# sk6812-24-12ring-out.net
KiCad netlist of a schematic drawn in EAGLE
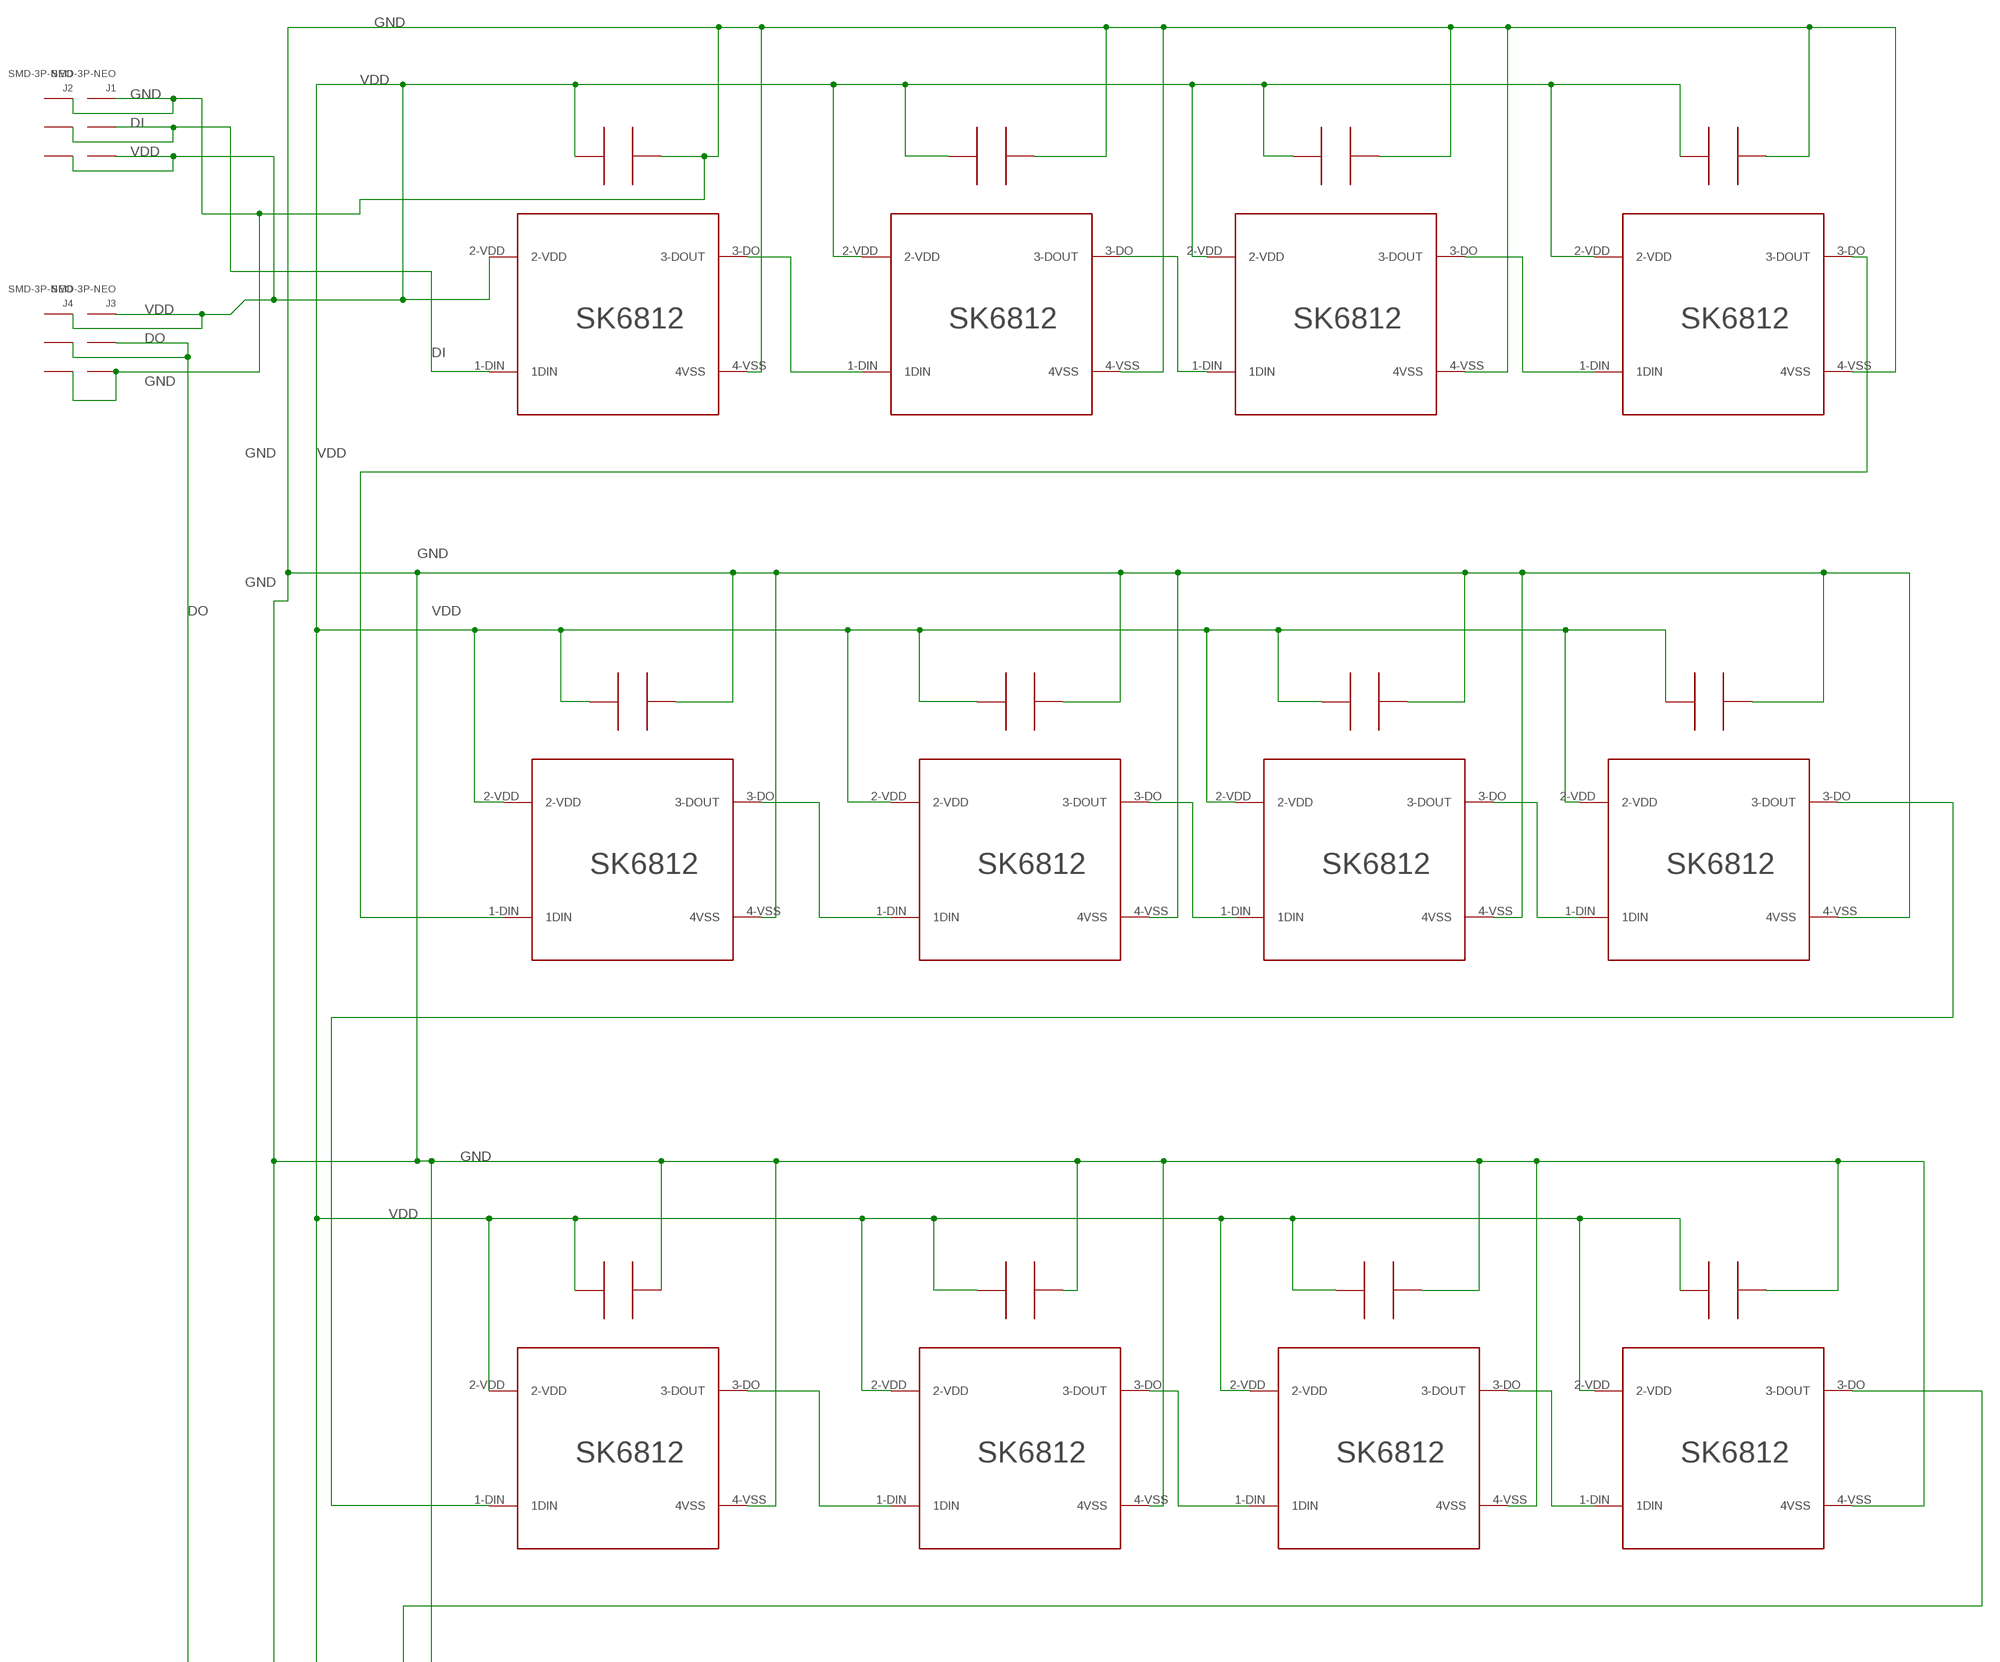
[diagram p0: schematic, sheet 1, part 1 of 2]
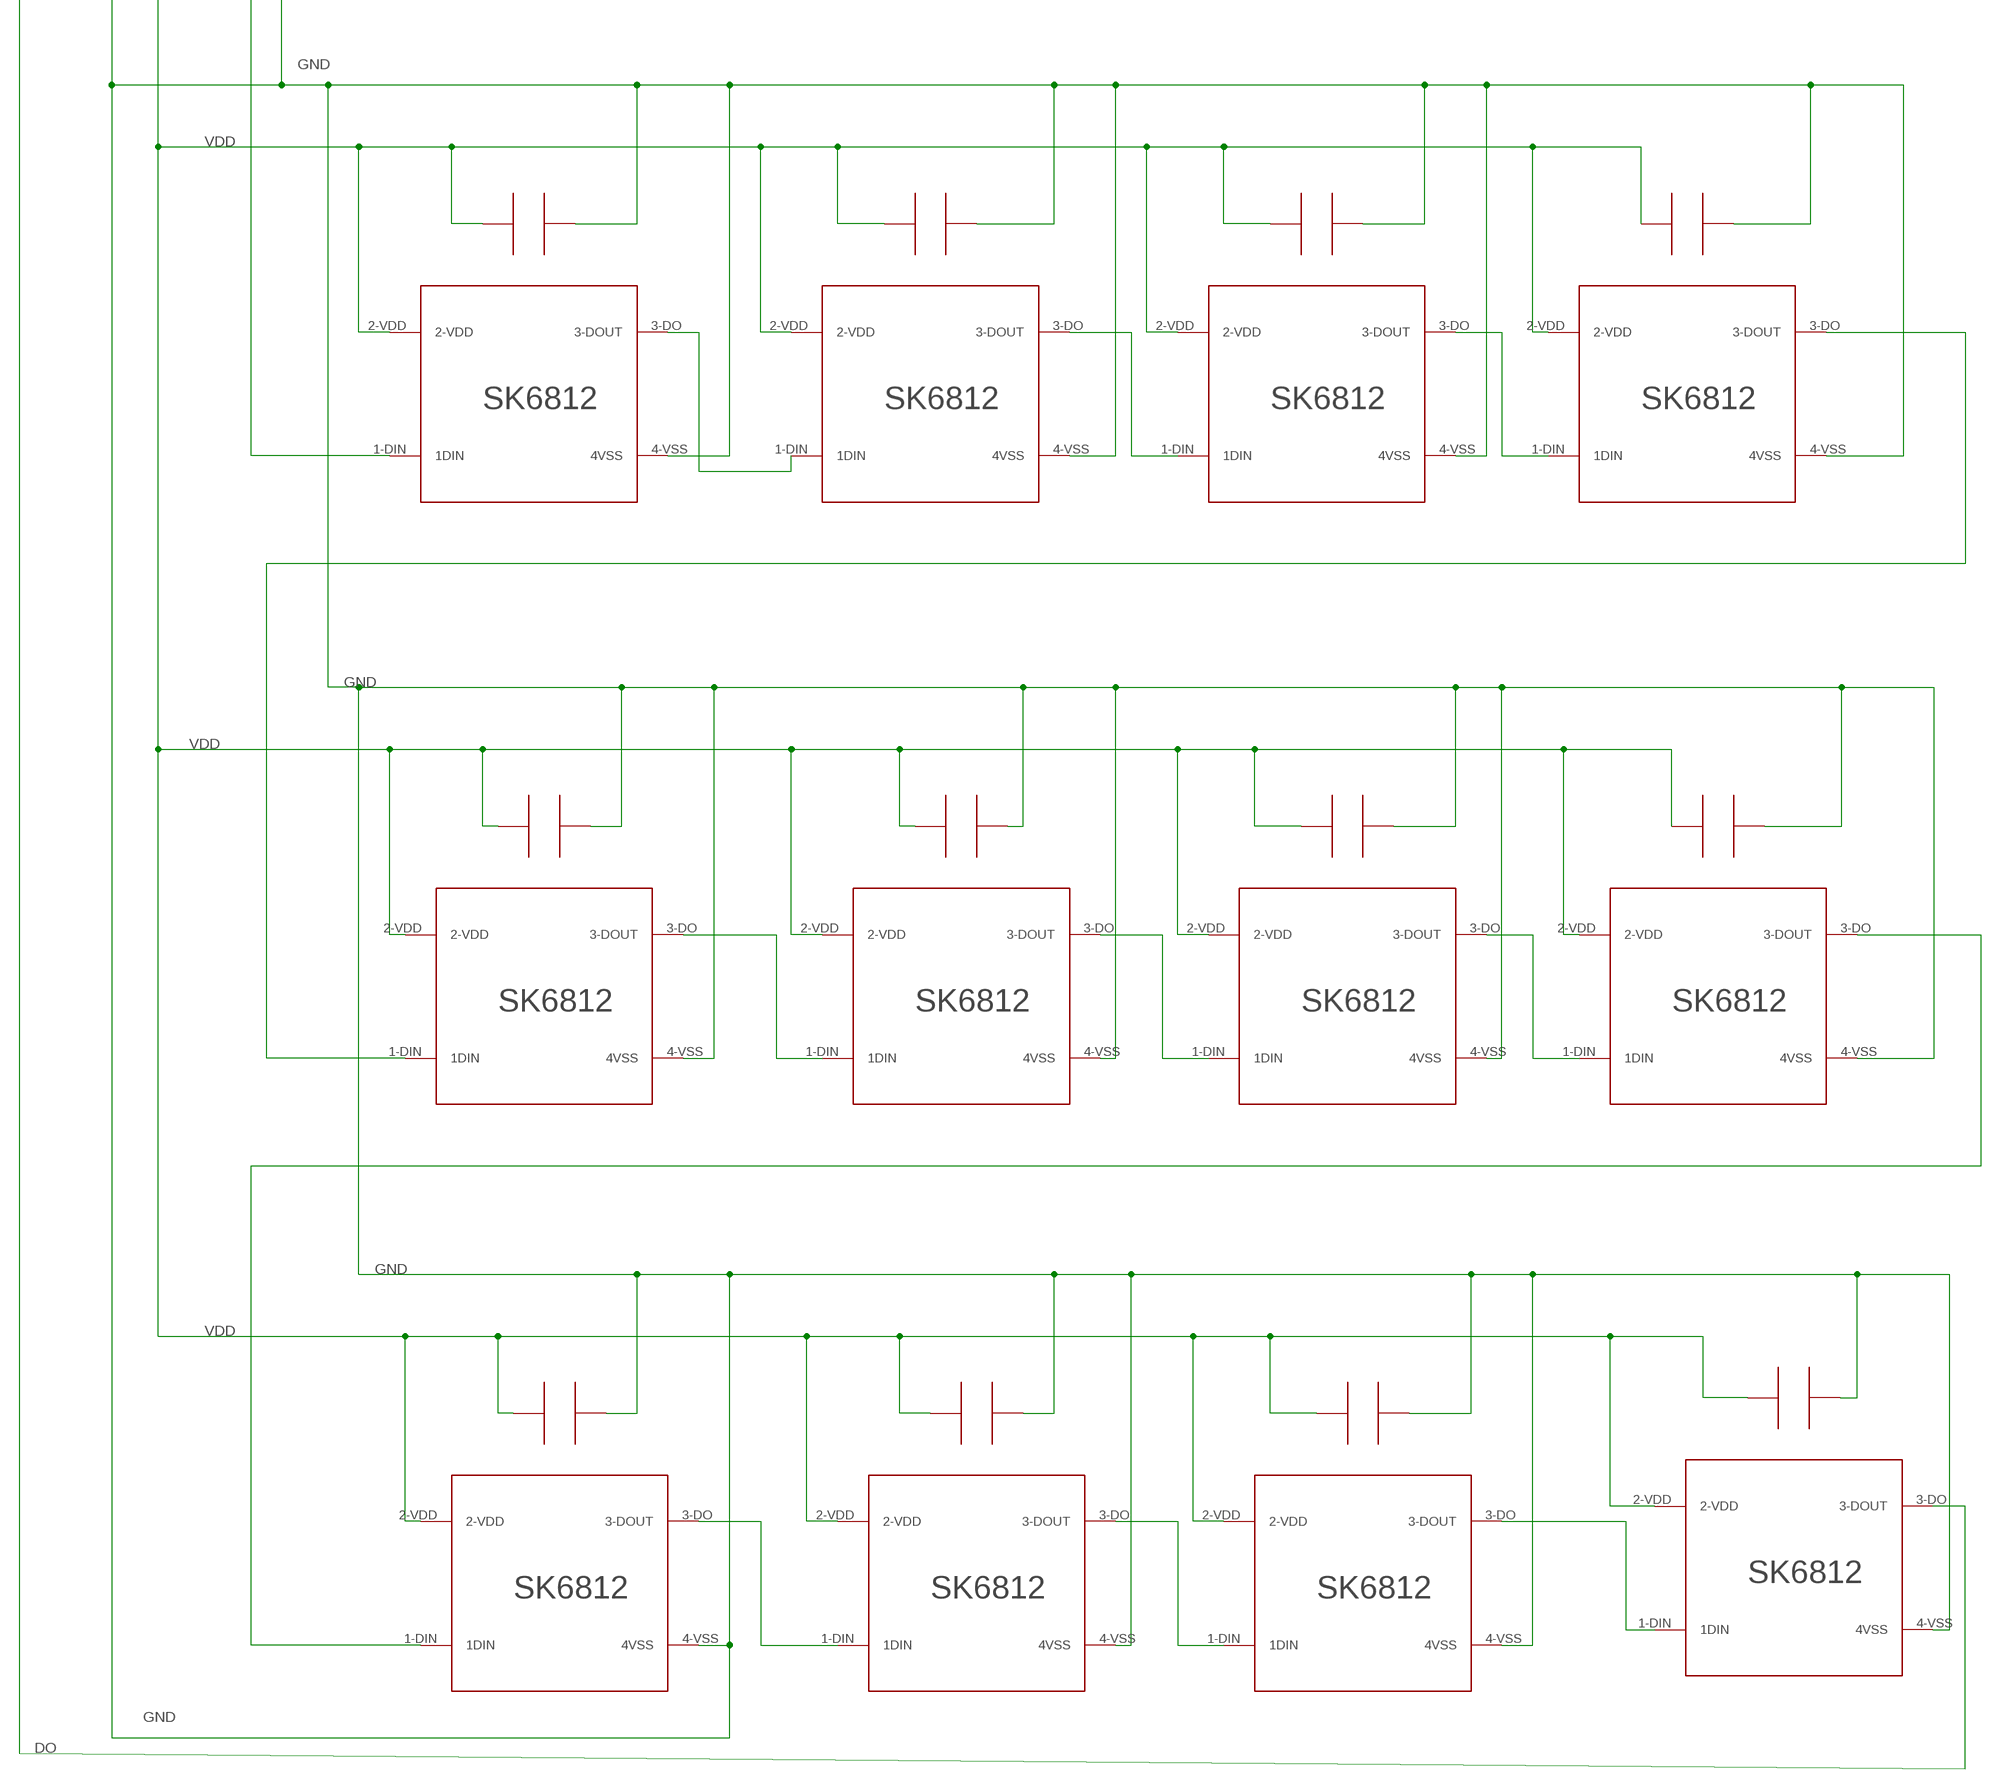
[diagram p1: schematic, sheet 1, part 2 of 2]

(export (version "E")
  (design (tool "Eeschema 10.0.6"))
  (components
    (comp (ref "D1")
      (value "SK6812-S-C")
      (footprint "eagle-import:SMD4020+0402C")
      (libsource (lib "eagle-import") (part "SK6812-S-C"))
    )
    (comp (ref "D2")
      (value "SK6812-S-C")
      (footprint "eagle-import:SMD4020+0402C")
      (libsource (lib "eagle-import") (part "SK6812-S-C"))
    )
    (comp (ref "D3")
      (value "SK6812-S-C")
      (footprint "eagle-import:SMD4020+0402C")
      (libsource (lib "eagle-import") (part "SK6812-S-C"))
    )
    (comp (ref "D4")
      (value "SK6812-S-C")
      (footprint "eagle-import:SMD4020+0402C")
      (libsource (lib "eagle-import") (part "SK6812-S-C"))
    )
    (comp (ref "D5")
      (value "SK6812-S-C")
      (footprint "eagle-import:SMD4020+0402C")
      (libsource (lib "eagle-import") (part "SK6812-S-C"))
    )
    (comp (ref "D6")
      (value "SK6812-S-C")
      (footprint "eagle-import:SMD4020+0402C")
      (libsource (lib "eagle-import") (part "SK6812-S-C"))
    )
    (comp (ref "D7")
      (value "SK6812-S-C")
      (footprint "eagle-import:SMD4020+0402C")
      (libsource (lib "eagle-import") (part "SK6812-S-C"))
    )
    (comp (ref "D8")
      (value "SK6812-S-C")
      (footprint "eagle-import:SMD4020+0402C")
      (libsource (lib "eagle-import") (part "SK6812-S-C"))
    )
    (comp (ref "D9")
      (value "SK6812-S-C")
      (footprint "eagle-import:SMD4020+0402C")
      (libsource (lib "eagle-import") (part "SK6812-S-C"))
    )
    (comp (ref "D10")
      (value "SK6812-S-C")
      (footprint "eagle-import:SMD4020+0402C")
      (libsource (lib "eagle-import") (part "SK6812-S-C"))
    )
    (comp (ref "D11")
      (value "SK6812-S-C")
      (footprint "eagle-import:SMD4020+0402C")
      (libsource (lib "eagle-import") (part "SK6812-S-C"))
    )
    (comp (ref "D12")
      (value "SK6812-S-C")
      (footprint "eagle-import:SMD4020+0402C")
      (libsource (lib "eagle-import") (part "SK6812-S-C"))
    )
    (comp (ref "D13")
      (value "SK6812-S-C")
      (footprint "eagle-import:SMD4020+0402C")
      (libsource (lib "eagle-import") (part "SK6812-S-C"))
    )
    (comp (ref "D14")
      (value "SK6812-S-C")
      (footprint "eagle-import:SMD4020+0402C")
      (libsource (lib "eagle-import") (part "SK6812-S-C"))
    )
    (comp (ref "D15")
      (value "SK6812-S-C")
      (footprint "eagle-import:SMD4020+0402C")
      (libsource (lib "eagle-import") (part "SK6812-S-C"))
    )
    (comp (ref "D16")
      (value "SK6812-S-C")
      (footprint "eagle-import:SMD4020+0402C")
      (libsource (lib "eagle-import") (part "SK6812-S-C"))
    )
    (comp (ref "D17")
      (value "SK6812-S-C")
      (footprint "eagle-import:SMD4020+0402C")
      (libsource (lib "eagle-import") (part "SK6812-S-C"))
    )
    (comp (ref "D18")
      (value "SK6812-S-C")
      (footprint "eagle-import:SMD4020+0402C")
      (libsource (lib "eagle-import") (part "SK6812-S-C"))
    )
    (comp (ref "D19")
      (value "SK6812-S-C")
      (footprint "eagle-import:SMD4020+0402C")
      (libsource (lib "eagle-import") (part "SK6812-S-C"))
    )
    (comp (ref "D20")
      (value "SK6812-S-C")
      (footprint "eagle-import:SMD4020+0402C")
      (libsource (lib "eagle-import") (part "SK6812-S-C"))
    )
    (comp (ref "D21")
      (value "SK6812-S-C")
      (footprint "eagle-import:SMD4020+0402C")
      (libsource (lib "eagle-import") (part "SK6812-S-C"))
    )
    (comp (ref "D22")
      (value "SK6812-S-C")
      (footprint "eagle-import:SMD4020+0402C")
      (libsource (lib "eagle-import") (part "SK6812-S-C"))
    )
    (comp (ref "D23")
      (value "SK6812-S-C")
      (footprint "eagle-import:SMD4020+0402C")
      (libsource (lib "eagle-import") (part "SK6812-S-C"))
    )
    (comp (ref "D24")
      (value "SK6812-S-C")
      (footprint "eagle-import:SMD4020+0402C")
      (libsource (lib "eagle-import") (part "SK6812-S-C"))
    )
    (comp (ref "J1")
      (value "SMD-3P-NEO")
      (footprint "eagle-import:SMD-3P-2.0")
      (libsource (lib "eagle-import") (part "SMD-3P-NEO"))
    )
    (comp (ref "J2")
      (value "SMD-3P-NEO")
      (footprint "eagle-import:SMD-3P-2.0")
      (libsource (lib "eagle-import") (part "SMD-3P-NEO"))
    )
    (comp (ref "J3")
      (value "SMD-3P-NEO")
      (footprint "eagle-import:SMD-3P-2.0")
      (libsource (lib "eagle-import") (part "SMD-3P-NEO"))
    )
    (comp (ref "J4")
      (value "SMD-3P-NEO")
      (footprint "eagle-import:SMD-3P-2.0")
      (libsource (lib "eagle-import") (part "SMD-3P-NEO"))
    )
  )
  (nets
    (net (code "1") (name "/DI") (class "Default")
      (node (ref "D1") (pin "1-DIN") (pinfunction "1DIN_1-DIN") (pintype "bidirectional"))
      (node (ref "J1") (pin "P$2") (pinfunction "2_P$2") (pintype "bidirectional"))
      (node (ref "J2") (pin "P$2") (pinfunction "2_P$2") (pintype "bidirectional"))
    )
    (net (code "2") (name "/DO") (class "Default")
      (node (ref "D24") (pin "3-DO") (pinfunction "3-DOUT_3-DO") (pintype "bidirectional"))
      (node (ref "J3") (pin "P$2") (pinfunction "2_P$2") (pintype "bidirectional"))
      (node (ref "J4") (pin "P$2") (pinfunction "2_P$2") (pintype "bidirectional"))
    )
    (net (code "3") (name "/GND") (class "Default")
      (node (ref "D1") (pin "4-VSS") (pinfunction "4VSS_4-VSS") (pintype "bidirectional"))
      (node (ref "D1") (pin "5-C-VSS") (pinfunction "C-VSS_5-C-VSS") (pintype "bidirectional"))
      (node (ref "D10") (pin "4-VSS") (pinfunction "4VSS_4-VSS") (pintype "bidirectional"))
      (node (ref "D10") (pin "5-C-VSS") (pinfunction "C-VSS_5-C-VSS") (pintype "bidirectional"))
      (node (ref "D11") (pin "4-VSS") (pinfunction "4VSS_4-VSS") (pintype "bidirectional"))
      (node (ref "D11") (pin "5-C-VSS") (pinfunction "C-VSS_5-C-VSS") (pintype "bidirectional"))
      (node (ref "D12") (pin "4-VSS") (pinfunction "4VSS_4-VSS") (pintype "bidirectional"))
      (node (ref "D12") (pin "5-C-VSS") (pinfunction "C-VSS_5-C-VSS") (pintype "bidirectional"))
      (node (ref "D13") (pin "4-VSS") (pinfunction "4VSS_4-VSS") (pintype "bidirectional"))
      (node (ref "D13") (pin "5-C-VSS") (pinfunction "C-VSS_5-C-VSS") (pintype "bidirectional"))
      (node (ref "D14") (pin "4-VSS") (pinfunction "4VSS_4-VSS") (pintype "bidirectional"))
      (node (ref "D14") (pin "5-C-VSS") (pinfunction "C-VSS_5-C-VSS") (pintype "bidirectional"))
      (node (ref "D15") (pin "4-VSS") (pinfunction "4VSS_4-VSS") (pintype "bidirectional"))
      (node (ref "D15") (pin "5-C-VSS") (pinfunction "C-VSS_5-C-VSS") (pintype "bidirectional"))
      (node (ref "D16") (pin "4-VSS") (pinfunction "4VSS_4-VSS") (pintype "bidirectional"))
      (node (ref "D16") (pin "5-C-VSS") (pinfunction "C-VSS_5-C-VSS") (pintype "bidirectional"))
      (node (ref "D17") (pin "4-VSS") (pinfunction "4VSS_4-VSS") (pintype "bidirectional"))
      (node (ref "D17") (pin "5-C-VSS") (pinfunction "C-VSS_5-C-VSS") (pintype "bidirectional"))
      (node (ref "D18") (pin "4-VSS") (pinfunction "4VSS_4-VSS") (pintype "bidirectional"))
      (node (ref "D18") (pin "5-C-VSS") (pinfunction "C-VSS_5-C-VSS") (pintype "bidirectional"))
      (node (ref "D19") (pin "4-VSS") (pinfunction "4VSS_4-VSS") (pintype "bidirectional"))
      (node (ref "D19") (pin "5-C-VSS") (pinfunction "C-VSS_5-C-VSS") (pintype "bidirectional"))
      (node (ref "D2") (pin "4-VSS") (pinfunction "4VSS_4-VSS") (pintype "bidirectional"))
      (node (ref "D2") (pin "5-C-VSS") (pinfunction "C-VSS_5-C-VSS") (pintype "bidirectional"))
      (node (ref "D20") (pin "4-VSS") (pinfunction "4VSS_4-VSS") (pintype "bidirectional"))
      (node (ref "D20") (pin "5-C-VSS") (pinfunction "C-VSS_5-C-VSS") (pintype "bidirectional"))
      (node (ref "D21") (pin "4-VSS") (pinfunction "4VSS_4-VSS") (pintype "bidirectional"))
      (node (ref "D21") (pin "5-C-VSS") (pinfunction "C-VSS_5-C-VSS") (pintype "bidirectional"))
      (node (ref "D22") (pin "4-VSS") (pinfunction "4VSS_4-VSS") (pintype "bidirectional"))
      (node (ref "D22") (pin "5-C-VSS") (pinfunction "C-VSS_5-C-VSS") (pintype "bidirectional"))
      (node (ref "D23") (pin "4-VSS") (pinfunction "4VSS_4-VSS") (pintype "bidirectional"))
      (node (ref "D23") (pin "5-C-VSS") (pinfunction "C-VSS_5-C-VSS") (pintype "bidirectional"))
      (node (ref "D24") (pin "4-VSS") (pinfunction "4VSS_4-VSS") (pintype "bidirectional"))
      (node (ref "D24") (pin "5-C-VSS") (pinfunction "C-VSS_5-C-VSS") (pintype "bidirectional"))
      (node (ref "D3") (pin "4-VSS") (pinfunction "4VSS_4-VSS") (pintype "bidirectional"))
      (node (ref "D3") (pin "5-C-VSS") (pinfunction "C-VSS_5-C-VSS") (pintype "bidirectional"))
      (node (ref "D4") (pin "4-VSS") (pinfunction "4VSS_4-VSS") (pintype "bidirectional"))
      (node (ref "D4") (pin "5-C-VSS") (pinfunction "C-VSS_5-C-VSS") (pintype "bidirectional"))
      (node (ref "D5") (pin "4-VSS") (pinfunction "4VSS_4-VSS") (pintype "bidirectional"))
      (node (ref "D5") (pin "5-C-VSS") (pinfunction "C-VSS_5-C-VSS") (pintype "bidirectional"))
      (node (ref "D6") (pin "4-VSS") (pinfunction "4VSS_4-VSS") (pintype "bidirectional"))
      (node (ref "D6") (pin "5-C-VSS") (pinfunction "C-VSS_5-C-VSS") (pintype "bidirectional"))
      (node (ref "D7") (pin "4-VSS") (pinfunction "4VSS_4-VSS") (pintype "bidirectional"))
      (node (ref "D7") (pin "5-C-VSS") (pinfunction "C-VSS_5-C-VSS") (pintype "bidirectional"))
      (node (ref "D8") (pin "4-VSS") (pinfunction "4VSS_4-VSS") (pintype "bidirectional"))
      (node (ref "D8") (pin "5-C-VSS") (pinfunction "C-VSS_5-C-VSS") (pintype "bidirectional"))
      (node (ref "D9") (pin "4-VSS") (pinfunction "4VSS_4-VSS") (pintype "bidirectional"))
      (node (ref "D9") (pin "5-C-VSS") (pinfunction "C-VSS_5-C-VSS") (pintype "bidirectional"))
      (node (ref "J1") (pin "P$3") (pinfunction "3_P$3") (pintype "bidirectional"))
      (node (ref "J2") (pin "P$3") (pinfunction "3_P$3") (pintype "bidirectional"))
      (node (ref "J3") (pin "P$1") (pinfunction "1_P$1") (pintype "bidirectional"))
      (node (ref "J4") (pin "P$1") (pinfunction "1_P$1") (pintype "bidirectional"))
    )
    (net (code "4") (name "/VDD") (class "Default")
      (node (ref "D1") (pin "2-VDD") (pinfunction "2-VDD_2-VDD") (pintype "bidirectional"))
      (node (ref "D1") (pin "6-C-VDD") (pinfunction "C-VDD_6-C-VDD") (pintype "bidirectional"))
      (node (ref "D10") (pin "2-VDD") (pinfunction "2-VDD_2-VDD") (pintype "bidirectional"))
      (node (ref "D10") (pin "6-C-VDD") (pinfunction "C-VDD_6-C-VDD") (pintype "bidirectional"))
      (node (ref "D11") (pin "2-VDD") (pinfunction "2-VDD_2-VDD") (pintype "bidirectional"))
      (node (ref "D11") (pin "6-C-VDD") (pinfunction "C-VDD_6-C-VDD") (pintype "bidirectional"))
      (node (ref "D12") (pin "2-VDD") (pinfunction "2-VDD_2-VDD") (pintype "bidirectional"))
      (node (ref "D12") (pin "6-C-VDD") (pinfunction "C-VDD_6-C-VDD") (pintype "bidirectional"))
      (node (ref "D13") (pin "2-VDD") (pinfunction "2-VDD_2-VDD") (pintype "bidirectional"))
      (node (ref "D13") (pin "6-C-VDD") (pinfunction "C-VDD_6-C-VDD") (pintype "bidirectional"))
      (node (ref "D14") (pin "2-VDD") (pinfunction "2-VDD_2-VDD") (pintype "bidirectional"))
      (node (ref "D14") (pin "6-C-VDD") (pinfunction "C-VDD_6-C-VDD") (pintype "bidirectional"))
      (node (ref "D15") (pin "2-VDD") (pinfunction "2-VDD_2-VDD") (pintype "bidirectional"))
      (node (ref "D15") (pin "6-C-VDD") (pinfunction "C-VDD_6-C-VDD") (pintype "bidirectional"))
      (node (ref "D16") (pin "2-VDD") (pinfunction "2-VDD_2-VDD") (pintype "bidirectional"))
      (node (ref "D16") (pin "6-C-VDD") (pinfunction "C-VDD_6-C-VDD") (pintype "bidirectional"))
      (node (ref "D17") (pin "2-VDD") (pinfunction "2-VDD_2-VDD") (pintype "bidirectional"))
      (node (ref "D17") (pin "6-C-VDD") (pinfunction "C-VDD_6-C-VDD") (pintype "bidirectional"))
      (node (ref "D18") (pin "2-VDD") (pinfunction "2-VDD_2-VDD") (pintype "bidirectional"))
      (node (ref "D18") (pin "6-C-VDD") (pinfunction "C-VDD_6-C-VDD") (pintype "bidirectional"))
      (node (ref "D19") (pin "2-VDD") (pinfunction "2-VDD_2-VDD") (pintype "bidirectional"))
      (node (ref "D19") (pin "6-C-VDD") (pinfunction "C-VDD_6-C-VDD") (pintype "bidirectional"))
      (node (ref "D2") (pin "2-VDD") (pinfunction "2-VDD_2-VDD") (pintype "bidirectional"))
      (node (ref "D2") (pin "6-C-VDD") (pinfunction "C-VDD_6-C-VDD") (pintype "bidirectional"))
      (node (ref "D20") (pin "2-VDD") (pinfunction "2-VDD_2-VDD") (pintype "bidirectional"))
      (node (ref "D20") (pin "6-C-VDD") (pinfunction "C-VDD_6-C-VDD") (pintype "bidirectional"))
      (node (ref "D21") (pin "2-VDD") (pinfunction "2-VDD_2-VDD") (pintype "bidirectional"))
      (node (ref "D21") (pin "6-C-VDD") (pinfunction "C-VDD_6-C-VDD") (pintype "bidirectional"))
      (node (ref "D22") (pin "2-VDD") (pinfunction "2-VDD_2-VDD") (pintype "bidirectional"))
      (node (ref "D22") (pin "6-C-VDD") (pinfunction "C-VDD_6-C-VDD") (pintype "bidirectional"))
      (node (ref "D23") (pin "2-VDD") (pinfunction "2-VDD_2-VDD") (pintype "bidirectional"))
      (node (ref "D23") (pin "6-C-VDD") (pinfunction "C-VDD_6-C-VDD") (pintype "bidirectional"))
      (node (ref "D24") (pin "2-VDD") (pinfunction "2-VDD_2-VDD") (pintype "bidirectional"))
      (node (ref "D24") (pin "6-C-VDD") (pinfunction "C-VDD_6-C-VDD") (pintype "bidirectional"))
      (node (ref "D3") (pin "2-VDD") (pinfunction "2-VDD_2-VDD") (pintype "bidirectional"))
      (node (ref "D3") (pin "6-C-VDD") (pinfunction "C-VDD_6-C-VDD") (pintype "bidirectional"))
      (node (ref "D4") (pin "2-VDD") (pinfunction "2-VDD_2-VDD") (pintype "bidirectional"))
      (node (ref "D4") (pin "6-C-VDD") (pinfunction "C-VDD_6-C-VDD") (pintype "bidirectional"))
      (node (ref "D5") (pin "2-VDD") (pinfunction "2-VDD_2-VDD") (pintype "bidirectional"))
      (node (ref "D5") (pin "6-C-VDD") (pinfunction "C-VDD_6-C-VDD") (pintype "bidirectional"))
      (node (ref "D6") (pin "2-VDD") (pinfunction "2-VDD_2-VDD") (pintype "bidirectional"))
      (node (ref "D6") (pin "6-C-VDD") (pinfunction "C-VDD_6-C-VDD") (pintype "bidirectional"))
      (node (ref "D7") (pin "2-VDD") (pinfunction "2-VDD_2-VDD") (pintype "bidirectional"))
      (node (ref "D7") (pin "6-C-VDD") (pinfunction "C-VDD_6-C-VDD") (pintype "bidirectional"))
      (node (ref "D8") (pin "2-VDD") (pinfunction "2-VDD_2-VDD") (pintype "bidirectional"))
      (node (ref "D8") (pin "6-C-VDD") (pinfunction "C-VDD_6-C-VDD") (pintype "bidirectional"))
      (node (ref "D9") (pin "2-VDD") (pinfunction "2-VDD_2-VDD") (pintype "bidirectional"))
      (node (ref "D9") (pin "6-C-VDD") (pinfunction "C-VDD_6-C-VDD") (pintype "bidirectional"))
      (node (ref "J1") (pin "P$1") (pinfunction "1_P$1") (pintype "bidirectional"))
      (node (ref "J2") (pin "P$1") (pinfunction "1_P$1") (pintype "bidirectional"))
      (node (ref "J3") (pin "P$3") (pinfunction "3_P$3") (pintype "bidirectional"))
      (node (ref "J4") (pin "P$3") (pinfunction "3_P$3") (pintype "bidirectional"))
    )
    (net (code "5") (name "Net-(D1-3-DOUT)") (class "Default")
      (node (ref "D1") (pin "3-DO") (pinfunction "3-DOUT_3-DO") (pintype "bidirectional"))
      (node (ref "D2") (pin "1-DIN") (pinfunction "1DIN_1-DIN") (pintype "bidirectional"))
    )
    (net (code "6") (name "Net-(D2-3-DOUT)") (class "Default")
      (node (ref "D2") (pin "3-DO") (pinfunction "3-DOUT_3-DO") (pintype "bidirectional"))
      (node (ref "D3") (pin "1-DIN") (pinfunction "1DIN_1-DIN") (pintype "bidirectional"))
    )
    (net (code "7") (name "Net-(D3-3-DOUT)") (class "Default")
      (node (ref "D3") (pin "3-DO") (pinfunction "3-DOUT_3-DO") (pintype "bidirectional"))
      (node (ref "D4") (pin "1-DIN") (pinfunction "1DIN_1-DIN") (pintype "bidirectional"))
    )
    (net (code "8") (name "Net-(D4-3-DOUT)") (class "Default")
      (node (ref "D4") (pin "3-DO") (pinfunction "3-DOUT_3-DO") (pintype "bidirectional"))
      (node (ref "D5") (pin "1-DIN") (pinfunction "1DIN_1-DIN") (pintype "bidirectional"))
    )
    (net (code "9") (name "Net-(D5-3-DOUT)") (class "Default")
      (node (ref "D5") (pin "3-DO") (pinfunction "3-DOUT_3-DO") (pintype "bidirectional"))
      (node (ref "D6") (pin "1-DIN") (pinfunction "1DIN_1-DIN") (pintype "bidirectional"))
    )
    (net (code "10") (name "Net-(D6-3-DOUT)") (class "Default")
      (node (ref "D6") (pin "3-DO") (pinfunction "3-DOUT_3-DO") (pintype "bidirectional"))
      (node (ref "D7") (pin "1-DIN") (pinfunction "1DIN_1-DIN") (pintype "bidirectional"))
    )
    (net (code "11") (name "Net-(D7-3-DOUT)") (class "Default")
      (node (ref "D7") (pin "3-DO") (pinfunction "3-DOUT_3-DO") (pintype "bidirectional"))
      (node (ref "D8") (pin "1-DIN") (pinfunction "1DIN_1-DIN") (pintype "bidirectional"))
    )
    (net (code "12") (name "Net-(D8-3-DOUT)") (class "Default")
      (node (ref "D8") (pin "3-DO") (pinfunction "3-DOUT_3-DO") (pintype "bidirectional"))
      (node (ref "D9") (pin "1-DIN") (pinfunction "1DIN_1-DIN") (pintype "bidirectional"))
    )
    (net (code "13") (name "Net-(D10-1DIN)") (class "Default")
      (node (ref "D10") (pin "1-DIN") (pinfunction "1DIN_1-DIN") (pintype "bidirectional"))
      (node (ref "D9") (pin "3-DO") (pinfunction "3-DOUT_3-DO") (pintype "bidirectional"))
    )
    (net (code "14") (name "Net-(D10-3-DOUT)") (class "Default")
      (node (ref "D10") (pin "3-DO") (pinfunction "3-DOUT_3-DO") (pintype "bidirectional"))
      (node (ref "D11") (pin "1-DIN") (pinfunction "1DIN_1-DIN") (pintype "bidirectional"))
    )
    (net (code "15") (name "Net-(D11-3-DOUT)") (class "Default")
      (node (ref "D11") (pin "3-DO") (pinfunction "3-DOUT_3-DO") (pintype "bidirectional"))
      (node (ref "D12") (pin "1-DIN") (pinfunction "1DIN_1-DIN") (pintype "bidirectional"))
    )
    (net (code "16") (name "Net-(D12-3-DOUT)") (class "Default")
      (node (ref "D12") (pin "3-DO") (pinfunction "3-DOUT_3-DO") (pintype "bidirectional"))
      (node (ref "D13") (pin "1-DIN") (pinfunction "1DIN_1-DIN") (pintype "bidirectional"))
    )
    (net (code "17") (name "Net-(D13-3-DOUT)") (class "Default")
      (node (ref "D13") (pin "3-DO") (pinfunction "3-DOUT_3-DO") (pintype "bidirectional"))
      (node (ref "D14") (pin "1-DIN") (pinfunction "1DIN_1-DIN") (pintype "bidirectional"))
    )
    (net (code "18") (name "Net-(D14-3-DOUT)") (class "Default")
      (node (ref "D14") (pin "3-DO") (pinfunction "3-DOUT_3-DO") (pintype "bidirectional"))
      (node (ref "D15") (pin "1-DIN") (pinfunction "1DIN_1-DIN") (pintype "bidirectional"))
    )
    (net (code "19") (name "Net-(D15-3-DOUT)") (class "Default")
      (node (ref "D15") (pin "3-DO") (pinfunction "3-DOUT_3-DO") (pintype "bidirectional"))
      (node (ref "D16") (pin "1-DIN") (pinfunction "1DIN_1-DIN") (pintype "bidirectional"))
    )
    (net (code "20") (name "Net-(D16-3-DOUT)") (class "Default")
      (node (ref "D16") (pin "3-DO") (pinfunction "3-DOUT_3-DO") (pintype "bidirectional"))
      (node (ref "D17") (pin "1-DIN") (pinfunction "1DIN_1-DIN") (pintype "bidirectional"))
    )
    (net (code "21") (name "Net-(D17-3-DOUT)") (class "Default")
      (node (ref "D17") (pin "3-DO") (pinfunction "3-DOUT_3-DO") (pintype "bidirectional"))
      (node (ref "D18") (pin "1-DIN") (pinfunction "1DIN_1-DIN") (pintype "bidirectional"))
    )
    (net (code "22") (name "Net-(D18-3-DOUT)") (class "Default")
      (node (ref "D18") (pin "3-DO") (pinfunction "3-DOUT_3-DO") (pintype "bidirectional"))
      (node (ref "D19") (pin "1-DIN") (pinfunction "1DIN_1-DIN") (pintype "bidirectional"))
    )
    (net (code "23") (name "Net-(D19-3-DOUT)") (class "Default")
      (node (ref "D19") (pin "3-DO") (pinfunction "3-DOUT_3-DO") (pintype "bidirectional"))
      (node (ref "D20") (pin "1-DIN") (pinfunction "1DIN_1-DIN") (pintype "bidirectional"))
    )
    (net (code "24") (name "Net-(D20-3-DOUT)") (class "Default")
      (node (ref "D20") (pin "3-DO") (pinfunction "3-DOUT_3-DO") (pintype "bidirectional"))
      (node (ref "D21") (pin "1-DIN") (pinfunction "1DIN_1-DIN") (pintype "bidirectional"))
    )
    (net (code "25") (name "Net-(D21-3-DOUT)") (class "Default")
      (node (ref "D21") (pin "3-DO") (pinfunction "3-DOUT_3-DO") (pintype "bidirectional"))
      (node (ref "D22") (pin "1-DIN") (pinfunction "1DIN_1-DIN") (pintype "bidirectional"))
    )
    (net (code "26") (name "Net-(D22-3-DOUT)") (class "Default")
      (node (ref "D22") (pin "3-DO") (pinfunction "3-DOUT_3-DO") (pintype "bidirectional"))
      (node (ref "D23") (pin "1-DIN") (pinfunction "1DIN_1-DIN") (pintype "bidirectional"))
    )
    (net (code "27") (name "Net-(D23-3-DOUT)") (class "Default")
      (node (ref "D23") (pin "3-DO") (pinfunction "3-DOUT_3-DO") (pintype "bidirectional"))
      (node (ref "D24") (pin "1-DIN") (pinfunction "1DIN_1-DIN") (pintype "bidirectional"))
    )
  )
)
